# Brain_Conn_Disconnect_all_on_one.net
KiCad netlist of a schematic drawn in EAGLE
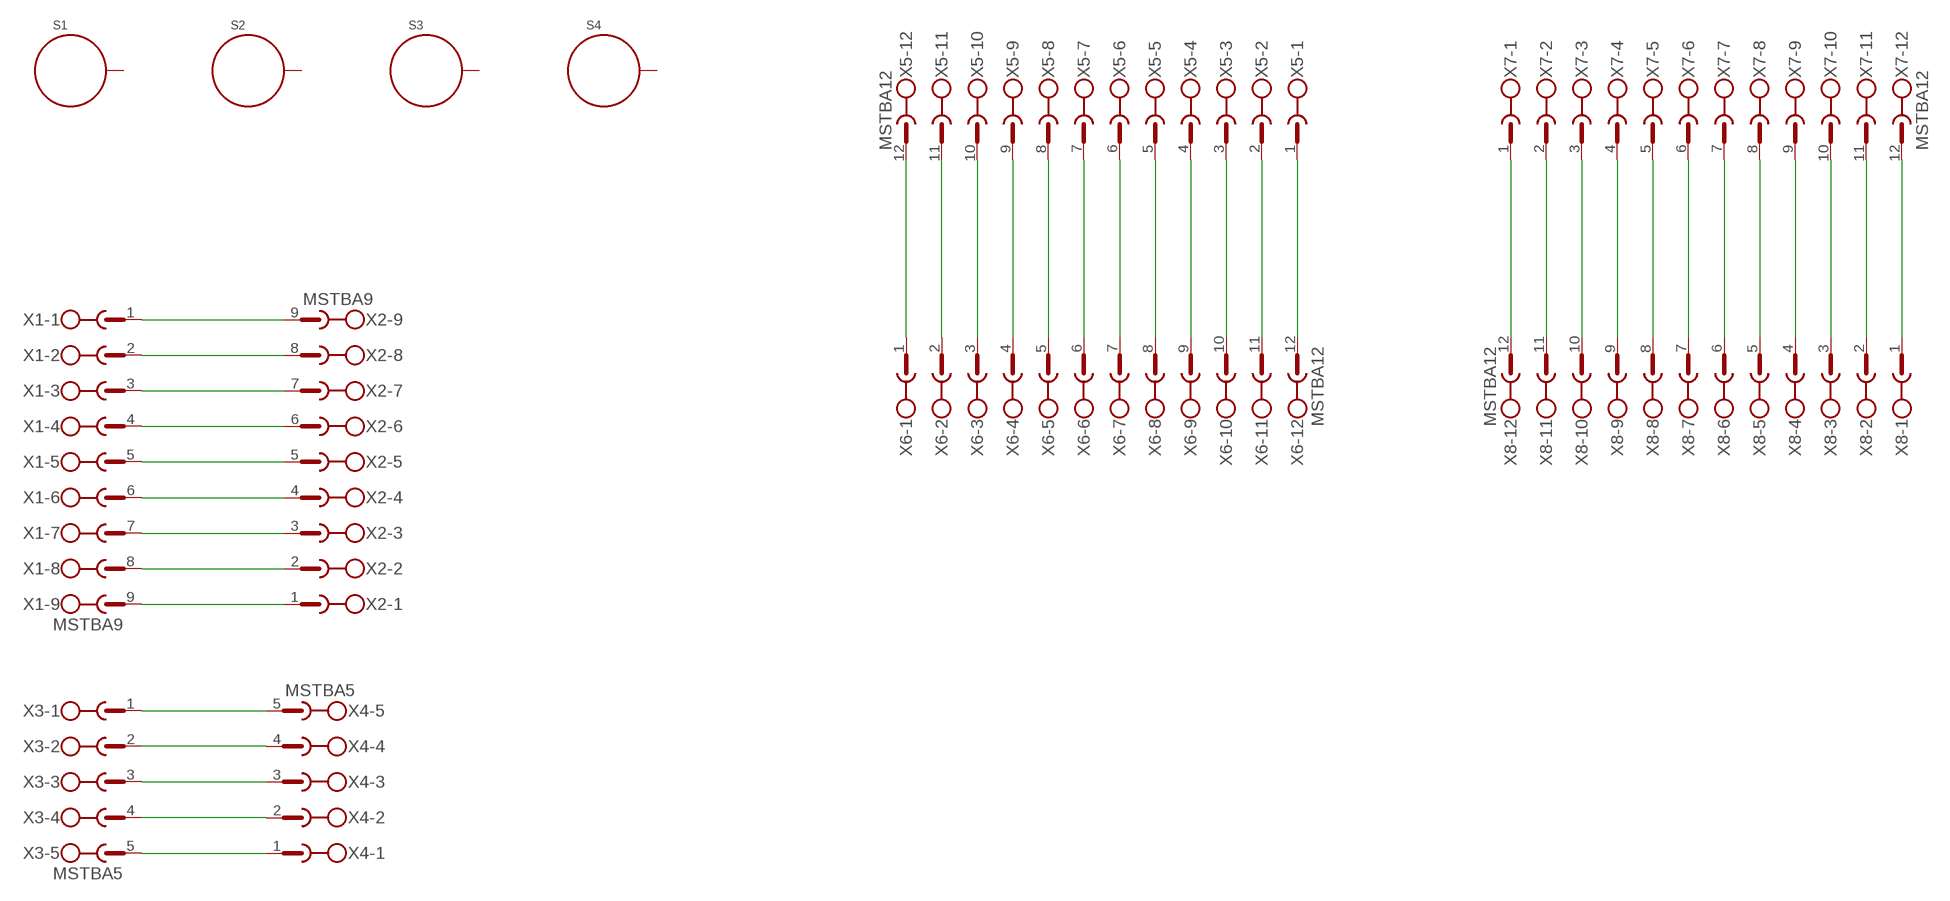
[diagram p0: schematic, sheet 1]

(export (version "E")
  (design (tool "Eeschema 10.0.6"))
  (components
    (comp (ref "S1")
      (value "STANDOFF_ELECTRICAL144")
      (footprint "eagle-import:STANDOFF_ELECTRICAL_144MILL_NORMAL_SCREW")
      (libsource (lib "eagle-import") (part "STANDOFF_ELECTRICAL144"))
    )
    (comp (ref "S2")
      (value "STANDOFF_ELECTRICAL144")
      (footprint "eagle-import:STANDOFF_ELECTRICAL_144MILL_NORMAL_SCREW")
      (libsource (lib "eagle-import") (part "STANDOFF_ELECTRICAL144"))
    )
    (comp (ref "S3")
      (value "STANDOFF_ELECTRICAL144")
      (footprint "eagle-import:STANDOFF_ELECTRICAL_144MILL_NORMAL_SCREW")
      (libsource (lib "eagle-import") (part "STANDOFF_ELECTRICAL144"))
    )
    (comp (ref "S4")
      (value "STANDOFF_ELECTRICAL144")
      (footprint "eagle-import:STANDOFF_ELECTRICAL_144MILL_NORMAL_SCREW")
      (libsource (lib "eagle-import") (part "STANDOFF_ELECTRICAL144"))
    )
    (comp (ref "X1")
      (value "MSTBA9")
      (footprint "eagle-import:MSTBA9")
      (fields (field (name "MF") "FARNELL") (field (name "MPN") "1757310"))
      (libsource (lib "eagle-import") (part "MSTBA9"))
    )
    (comp (ref "X2")
      (value "MSTBA9")
      (footprint "eagle-import:MSTBA9")
      (fields (field (name "MF") "FARNELL") (field (name "MPN") "1757310"))
      (libsource (lib "eagle-import") (part "MSTBA9"))
    )
    (comp (ref "X3")
      (value "MSTBA5")
      (footprint "eagle-import:MSTBA5")
      (fields (field (name "MPN") "1757271"))
      (libsource (lib "eagle-import") (part "MSTBA5"))
    )
    (comp (ref "X4")
      (value "MSTBA5")
      (footprint "eagle-import:MSTBA5")
      (fields (field (name "MPN") "1757271"))
      (libsource (lib "eagle-import") (part "MSTBA5"))
    )
    (comp (ref "X5")
      (value "MSTBA12")
      (footprint "eagle-import:MSTBA12")
      (fields (field (name "MPN") "1757349"))
      (libsource (lib "eagle-import") (part "MSTBA12"))
    )
    (comp (ref "X6")
      (value "MSTBA12")
      (footprint "eagle-import:MSTBA12")
      (fields (field (name "MPN") "1757349"))
      (libsource (lib "eagle-import") (part "MSTBA12"))
    )
    (comp (ref "X7")
      (value "MSTBA12")
      (footprint "eagle-import:MSTBA12")
      (fields (field (name "MPN") "1757349"))
      (libsource (lib "eagle-import") (part "MSTBA12"))
    )
    (comp (ref "X8")
      (value "MSTBA12")
      (footprint "eagle-import:MSTBA12")
      (fields (field (name "MPN") "1757349"))
      (libsource (lib "eagle-import") (part "MSTBA12"))
    )
  )
  (nets
    (net (code "1") (name "Net-(X1B-1)") (class "Default")
      (node (ref "X1") (pin "2") (pinfunction "1_2") (pintype "passive"))
      (node (ref "X2") (pin "8") (pinfunction "1_8") (pintype "passive"))
    )
    (net (code "2") (name "Net-(X1C-1)") (class "Default")
      (node (ref "X1") (pin "3") (pinfunction "1_3") (pintype "passive"))
      (node (ref "X2") (pin "7") (pinfunction "1_7") (pintype "passive"))
    )
    (net (code "3") (name "Net-(X1D-1)") (class "Default")
      (node (ref "X1") (pin "4") (pinfunction "1_4") (pintype "passive"))
      (node (ref "X2") (pin "6") (pinfunction "1_6") (pintype "passive"))
    )
    (net (code "4") (name "Net-(X1E-1)") (class "Default")
      (node (ref "X1") (pin "5") (pinfunction "1_5") (pintype "passive"))
      (node (ref "X2") (pin "5") (pinfunction "1_5") (pintype "passive"))
    )
    (net (code "5") (name "Net-(X1F-1)") (class "Default")
      (node (ref "X1") (pin "6") (pinfunction "1_6") (pintype "passive"))
      (node (ref "X2") (pin "4") (pinfunction "1_4") (pintype "passive"))
    )
    (net (code "6") (name "Net-(X1G-1)") (class "Default")
      (node (ref "X1") (pin "7") (pinfunction "1_7") (pintype "passive"))
      (node (ref "X2") (pin "3") (pinfunction "1_3") (pintype "passive"))
    )
    (net (code "7") (name "Net-(X1H-1)") (class "Default")
      (node (ref "X1") (pin "8") (pinfunction "1_8") (pintype "passive"))
      (node (ref "X2") (pin "2") (pinfunction "1_2") (pintype "passive"))
    )
    (net (code "8") (name "Net-(X1I-1)") (class "Default")
      (node (ref "X1") (pin "9") (pinfunction "1_9") (pintype "passive"))
      (node (ref "X2") (pin "1") (pinfunction "1_1") (pintype "passive"))
    )
    (net (code "9") (name "Net-(X2I-1)") (class "Default")
      (node (ref "X1") (pin "1") (pinfunction "1_1") (pintype "passive"))
      (node (ref "X2") (pin "9") (pinfunction "1_9") (pintype "passive"))
    )
    (net (code "10") (name "Net-(X3B-1)") (class "Default")
      (node (ref "X3") (pin "2") (pinfunction "1_2") (pintype "passive"))
      (node (ref "X4") (pin "4") (pinfunction "1_4") (pintype "passive"))
    )
    (net (code "11") (name "Net-(X3C-1)") (class "Default")
      (node (ref "X3") (pin "3") (pinfunction "1_3") (pintype "passive"))
      (node (ref "X4") (pin "3") (pinfunction "1_3") (pintype "passive"))
    )
    (net (code "12") (name "Net-(X3D-1)") (class "Default")
      (node (ref "X3") (pin "4") (pinfunction "1_4") (pintype "passive"))
      (node (ref "X4") (pin "2") (pinfunction "1_2") (pintype "passive"))
    )
    (net (code "13") (name "Net-(X3E-1)") (class "Default")
      (node (ref "X3") (pin "5") (pinfunction "1_5") (pintype "passive"))
      (node (ref "X4") (pin "1") (pinfunction "1_1") (pintype "passive"))
    )
    (net (code "14") (name "Net-(X4E-1)") (class "Default")
      (node (ref "X3") (pin "1") (pinfunction "1_1") (pintype "passive"))
      (node (ref "X4") (pin "5") (pinfunction "1_5") (pintype "passive"))
    )
    (net (code "15") (name "Net-(X5B-1)") (class "Default")
      (node (ref "X5") (pin "10") (pinfunction "1_10") (pintype "passive"))
      (node (ref "X6") (pin "3") (pinfunction "1_3") (pintype "passive"))
    )
    (net (code "16") (name "Net-(X5C-1)") (class "Default")
      (node (ref "X5") (pin "11") (pinfunction "1_11") (pintype "passive"))
      (node (ref "X6") (pin "2") (pinfunction "1_2") (pintype "passive"))
    )
    (net (code "17") (name "Net-(X5D-1)") (class "Default")
      (node (ref "X5") (pin "12") (pinfunction "1_12") (pintype "passive"))
      (node (ref "X6") (pin "1") (pinfunction "1_1") (pintype "passive"))
    )
    (net (code "18") (name "Net-(X5E-1)") (class "Default")
      (node (ref "X5") (pin "2") (pinfunction "1_2") (pintype "passive"))
      (node (ref "X6") (pin "11") (pinfunction "1_11") (pintype "passive"))
    )
    (net (code "19") (name "Net-(X5F-1)") (class "Default")
      (node (ref "X5") (pin "3") (pinfunction "1_3") (pintype "passive"))
      (node (ref "X6") (pin "10") (pinfunction "1_10") (pintype "passive"))
    )
    (net (code "20") (name "Net-(X5G-1)") (class "Default")
      (node (ref "X5") (pin "4") (pinfunction "1_4") (pintype "passive"))
      (node (ref "X6") (pin "9") (pinfunction "1_9") (pintype "passive"))
    )
    (net (code "21") (name "Net-(X5H-1)") (class "Default")
      (node (ref "X5") (pin "5") (pinfunction "1_5") (pintype "passive"))
      (node (ref "X6") (pin "8") (pinfunction "1_8") (pintype "passive"))
    )
    (net (code "22") (name "Net-(X5I-1)") (class "Default")
      (node (ref "X5") (pin "6") (pinfunction "1_6") (pintype "passive"))
      (node (ref "X6") (pin "7") (pinfunction "1_7") (pintype "passive"))
    )
    (net (code "23") (name "Net-(X5J-1)") (class "Default")
      (node (ref "X5") (pin "7") (pinfunction "1_7") (pintype "passive"))
      (node (ref "X6") (pin "6") (pinfunction "1_6") (pintype "passive"))
    )
    (net (code "24") (name "Net-(X5K-1)") (class "Default")
      (node (ref "X5") (pin "8") (pinfunction "1_8") (pintype "passive"))
      (node (ref "X6") (pin "5") (pinfunction "1_5") (pintype "passive"))
    )
    (net (code "25") (name "Net-(X5L-1)") (class "Default")
      (node (ref "X5") (pin "9") (pinfunction "1_9") (pintype "passive"))
      (node (ref "X6") (pin "4") (pinfunction "1_4") (pintype "passive"))
    )
    (net (code "26") (name "Net-(X6D-1)") (class "Default")
      (node (ref "X5") (pin "1") (pinfunction "1_1") (pintype "passive"))
      (node (ref "X6") (pin "12") (pinfunction "1_12") (pintype "passive"))
    )
    (net (code "27") (name "Net-(X7B-1)") (class "Default")
      (node (ref "X7") (pin "10") (pinfunction "1_10") (pintype "passive"))
      (node (ref "X8") (pin "3") (pinfunction "1_3") (pintype "passive"))
    )
    (net (code "28") (name "Net-(X7C-1)") (class "Default")
      (node (ref "X7") (pin "11") (pinfunction "1_11") (pintype "passive"))
      (node (ref "X8") (pin "2") (pinfunction "1_2") (pintype "passive"))
    )
    (net (code "29") (name "Net-(X7D-1)") (class "Default")
      (node (ref "X7") (pin "12") (pinfunction "1_12") (pintype "passive"))
      (node (ref "X8") (pin "1") (pinfunction "1_1") (pintype "passive"))
    )
    (net (code "30") (name "Net-(X7E-1)") (class "Default")
      (node (ref "X7") (pin "2") (pinfunction "1_2") (pintype "passive"))
      (node (ref "X8") (pin "11") (pinfunction "1_11") (pintype "passive"))
    )
    (net (code "31") (name "Net-(X7F-1)") (class "Default")
      (node (ref "X7") (pin "3") (pinfunction "1_3") (pintype "passive"))
      (node (ref "X8") (pin "10") (pinfunction "1_10") (pintype "passive"))
    )
    (net (code "32") (name "Net-(X7G-1)") (class "Default")
      (node (ref "X7") (pin "4") (pinfunction "1_4") (pintype "passive"))
      (node (ref "X8") (pin "9") (pinfunction "1_9") (pintype "passive"))
    )
    (net (code "33") (name "Net-(X7H-1)") (class "Default")
      (node (ref "X7") (pin "5") (pinfunction "1_5") (pintype "passive"))
      (node (ref "X8") (pin "8") (pinfunction "1_8") (pintype "passive"))
    )
    (net (code "34") (name "Net-(X7I-1)") (class "Default")
      (node (ref "X7") (pin "6") (pinfunction "1_6") (pintype "passive"))
      (node (ref "X8") (pin "7") (pinfunction "1_7") (pintype "passive"))
    )
    (net (code "35") (name "Net-(X7J-1)") (class "Default")
      (node (ref "X7") (pin "7") (pinfunction "1_7") (pintype "passive"))
      (node (ref "X8") (pin "6") (pinfunction "1_6") (pintype "passive"))
    )
    (net (code "36") (name "Net-(X7K-1)") (class "Default")
      (node (ref "X7") (pin "8") (pinfunction "1_8") (pintype "passive"))
      (node (ref "X8") (pin "5") (pinfunction "1_5") (pintype "passive"))
    )
    (net (code "37") (name "Net-(X7L-1)") (class "Default")
      (node (ref "X7") (pin "9") (pinfunction "1_9") (pintype "passive"))
      (node (ref "X8") (pin "4") (pinfunction "1_4") (pintype "passive"))
    )
    (net (code "38") (name "Net-(X8D-1)") (class "Default")
      (node (ref "X7") (pin "1") (pinfunction "1_1") (pintype "passive"))
      (node (ref "X8") (pin "12") (pinfunction "1_12") (pintype "passive"))
    )
    (net (code "39") (name "unconnected-(S1-P$1-PadP1)") (class "Default")
      (node (ref "S1") (pin "P1") (pinfunction "P$1_P1") (pintype "bidirectional"))
    )
    (net (code "40") (name "unconnected-(S2-P$1-PadP1)") (class "Default")
      (node (ref "S2") (pin "P1") (pinfunction "P$1_P1") (pintype "bidirectional"))
    )
    (net (code "41") (name "unconnected-(S3-P$1-PadP1)") (class "Default")
      (node (ref "S3") (pin "P1") (pinfunction "P$1_P1") (pintype "bidirectional"))
    )
    (net (code "42") (name "unconnected-(S4-P$1-PadP1)") (class "Default")
      (node (ref "S4") (pin "P1") (pinfunction "P$1_P1") (pintype "bidirectional"))
    )
  )
)
